# CustomTP4056Module.net
KiCad netlist of a schematic drawn in Altium Designer
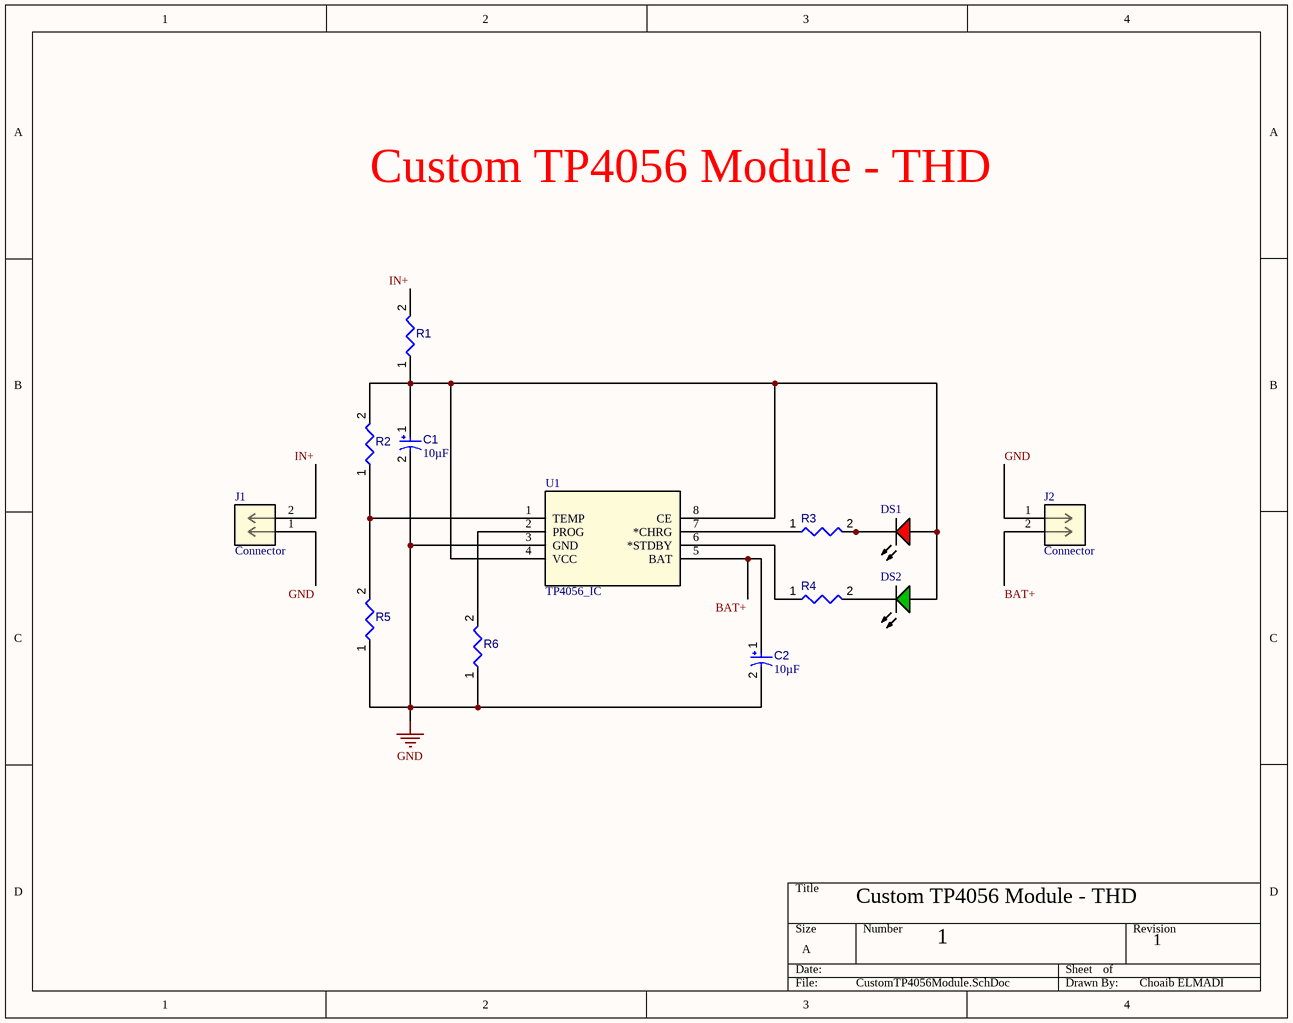
[diagram p0: CustomTP4056Module.SchDoc]

(export (version "E")
  (design (tool "Eeschema 10.0.6"))
  (components
    (comp (ref "C1")
      (value "10µF")
      (footprint "CAPPR55-200-1100X500X1200")
      (description "Aluminum Electrolytic Capacitor, 10 uF, +/- 20%, 50 V, -40 to 85 degC, 2-Pin THD, RoHS, Bulk")
      (fields (field (name "MANUFACTURER") "Panasonic") (field (name "TOLERANCE") "20%"))
      (libsource (lib "Altium Space") (part "CAP-P-2"))
    )
    (comp (ref "C2")
      (value "10µF")
      (footprint "CAPPR55-200-1100X500X1200")
      (description "Aluminum Electrolytic Capacitor, 10 uF, +/- 20%, 50 V, -40 to 85 degC, 2-Pin THD, RoHS, Bulk")
      (fields (field (name "MANUFACTURER") "Panasonic") (field (name "TOLERANCE") "20%"))
      (libsource (lib "Altium Space") (part "CAP-P-2"))
    )
    (comp (ref "DS1")
      (value "LTL-1CHE")
      (footprint "INDPR60-254-520X380X650")
      (description "LED Uni-Color Red, 100 mW, 30 mA, -55 to 100 degC, 2-Pin THD, RoHS, Bulk")
      (fields (field (name "MANUFACTURER") "Lite-On"))
      (libsource (lib "Altium Space") (part "LED-RED-AK-2"))
    )
    (comp (ref "DS2")
      (value "LTL-1CHG")
      (footprint "LTST-LTL-1CHG-2")
      (description "LED Uni-Color Green, 100 mW, 30 mA, -55 to 100 degC, 2-Pin THD, RoHS, Bulk")
      (fields (field (name "POWER") "100mW") (field (name "MANUFACTURER") "Lite-On"))
      (libsource (lib "Altium Space") (part "LED-GREEN-AK-2"))
    )
    (comp (ref "J1")
      (value "Connector")
      (footprint "CONN_M20-99902_HRW")
      (description "No Description Available")
      (libsource (lib "") (part "M20-9990245_1"))
    )
    (comp (ref "J2")
      (value "Connector")
      (footprint "CONN_M20-99902_HRW")
      (description "No Description Available")
      (libsource (lib "M20-9990245") (part "M20-9990245"))
    )
    (comp (ref "R1")
      (value "MFR-25FBF52-475R")
      (footprint "RESA60-630X240")
      (description "Axial Resistor, 220 Ohm, +/- 1%, 0.25 W, -55 to 155 degC, 2-Pin THD, RoHS, Bulk")
      (fields (field (name "MANUFACTURER") "Yageo") (field (name "TOLERANCE") "1%"))
      (libsource (lib "Altium Space") (part "RES-2"))
    )
    (comp (ref "R2")
      (value "MFR-25FBF52-475R")
      (footprint "RESA60-630X240")
      (description "Axial Resistor, 220 Ohm, +/- 1%, 0.25 W, -55 to 155 degC, 2-Pin THD, RoHS, Bulk")
      (fields (field (name "MANUFACTURER") "Yageo") (field (name "TOLERANCE") "1%"))
      (libsource (lib "Altium Space") (part "RES-2"))
    )
    (comp (ref "R3")
      (value "MFR-25FBF52-475R")
      (footprint "RESA60-630X240")
      (description "Axial Resistor, 220 Ohm, +/- 1%, 0.25 W, -55 to 155 degC, 2-Pin THD, RoHS, Bulk")
      (fields (field (name "MANUFACTURER") "Yageo") (field (name "TOLERANCE") "1%"))
      (libsource (lib "Altium Space") (part "RES-2"))
    )
    (comp (ref "R4")
      (value "MFR-25FBF52-475R")
      (footprint "RESA60-630X240")
      (description "Axial Resistor, 220 Ohm, +/- 1%, 0.25 W, -55 to 155 degC, 2-Pin THD, RoHS, Bulk")
      (fields (field (name "MANUFACTURER") "Yageo") (field (name "TOLERANCE") "1%"))
      (libsource (lib "Altium Space") (part "RES-2"))
    )
    (comp (ref "R5")
      (value "MFR-25FBF52-475R")
      (footprint "RESA60-630X240")
      (description "Axial Resistor, 220 Ohm, +/- 1%, 0.25 W, -55 to 155 degC, 2-Pin THD, RoHS, Bulk")
      (fields (field (name "MANUFACTURER") "Yageo") (field (name "TOLERANCE") "1%"))
      (libsource (lib "Altium Space") (part "RES-2"))
    )
    (comp (ref "R6")
      (value "MFR-25FBF52-475R")
      (footprint "RESA60-630X240")
      (description "Axial Resistor, 220 Ohm, +/- 1%, 0.25 W, -55 to 155 degC, 2-Pin THD, RoHS, Bulk")
      (fields (field (name "MANUFACTURER") "Yageo") (field (name "TOLERANCE") "1%"))
      (libsource (lib "Altium Space") (part "RES-2"))
    )
    (comp (ref "U1")
      (value "TP4056_IC")
      (footprint "DIP-8_STM")
      (description "No Description Available")
      (libsource (lib "NE555N") (part "NE555N"))
    )
  )
  (nets
    (net (code "1") (name "/BAT+") (class "Default")
      (node (ref "C2") (pin "1") (pinfunction "1_1") (pintype "passive"))
      (node (ref "J2") (pin "2") (pinfunction "2_2") (pintype "passive"))
      (node (ref "U1") (pin "5") (pinfunction "BAT_5") (pintype "passive"))
    )
    (net (code "2") (name "/IN+") (class "Default")
      (node (ref "J1") (pin "2") (pinfunction "2_2") (pintype "passive"))
      (node (ref "R1") (pin "2") (pinfunction "2_2") (pintype "passive"))
    )
    (net (code "3") (name "GND") (class "Default")
      (node (ref "C1") (pin "2") (pinfunction "2_2") (pintype "passive"))
      (node (ref "C2") (pin "2") (pinfunction "2_2") (pintype "passive"))
      (node (ref "J1") (pin "1") (pinfunction "1_1") (pintype "passive"))
      (node (ref "J2") (pin "1") (pinfunction "1_1") (pintype "passive"))
      (node (ref "R5") (pin "1") (pinfunction "1_1") (pintype "passive"))
      (node (ref "R6") (pin "1") (pinfunction "1_1") (pintype "passive"))
      (node (ref "U1") (pin "3") (pinfunction "GND_3") (pintype "power_in"))
    )
    (net (code "4") (name "Net-(DS1-A)") (class "Default")
      (node (ref "C1") (pin "1") (pinfunction "1_1") (pintype "passive"))
      (node (ref "DS1") (pin "1") (pinfunction "A_1") (pintype "passive"))
      (node (ref "DS2") (pin "1") (pinfunction "A_1") (pintype "passive"))
      (node (ref "R1") (pin "1") (pinfunction "1_1") (pintype "passive"))
      (node (ref "R2") (pin "2") (pinfunction "2_2") (pintype "passive"))
      (node (ref "U1") (pin "4") (pinfunction "VCC_4") (pintype "power_in"))
      (node (ref "U1") (pin "8") (pinfunction "CE_8") (pintype "passive"))
    )
    (net (code "5") (name "Net-(DS1-K)") (class "Default")
      (node (ref "DS1") (pin "2") (pinfunction "K_2") (pintype "passive"))
      (node (ref "R3") (pin "2") (pinfunction "2_2") (pintype "passive"))
    )
    (net (code "6") (name "Net-(DS2-K)") (class "Default")
      (node (ref "DS2") (pin "2") (pinfunction "K_2") (pintype "passive"))
      (node (ref "R4") (pin "2") (pinfunction "2_2") (pintype "passive"))
    )
    (net (code "7") (name "Net-(U1-*CHRG)") (class "Default")
      (node (ref "R3") (pin "1") (pinfunction "1_1") (pintype "passive"))
      (node (ref "U1") (pin "7") (pinfunction "*CHRG_7") (pintype "passive"))
    )
    (net (code "8") (name "Net-(U1-*STDBY)") (class "Default")
      (node (ref "R4") (pin "1") (pinfunction "1_1") (pintype "passive"))
      (node (ref "U1") (pin "6") (pinfunction "*STDBY_6") (pintype "passive"))
    )
    (net (code "9") (name "Net-(U1-PROG)") (class "Default")
      (node (ref "R6") (pin "2") (pinfunction "2_2") (pintype "passive"))
      (node (ref "U1") (pin "2") (pinfunction "PROG_2") (pintype "passive"))
    )
    (net (code "10") (name "Net-(U1-TEMP)") (class "Default")
      (node (ref "R2") (pin "1") (pinfunction "1_1") (pintype "passive"))
      (node (ref "R5") (pin "2") (pinfunction "2_2") (pintype "passive"))
      (node (ref "U1") (pin "1") (pinfunction "TEMP_1") (pintype "passive"))
    )
  )
)
